# USB_ow.net
KiCad netlist of a schematic drawn in EAGLE
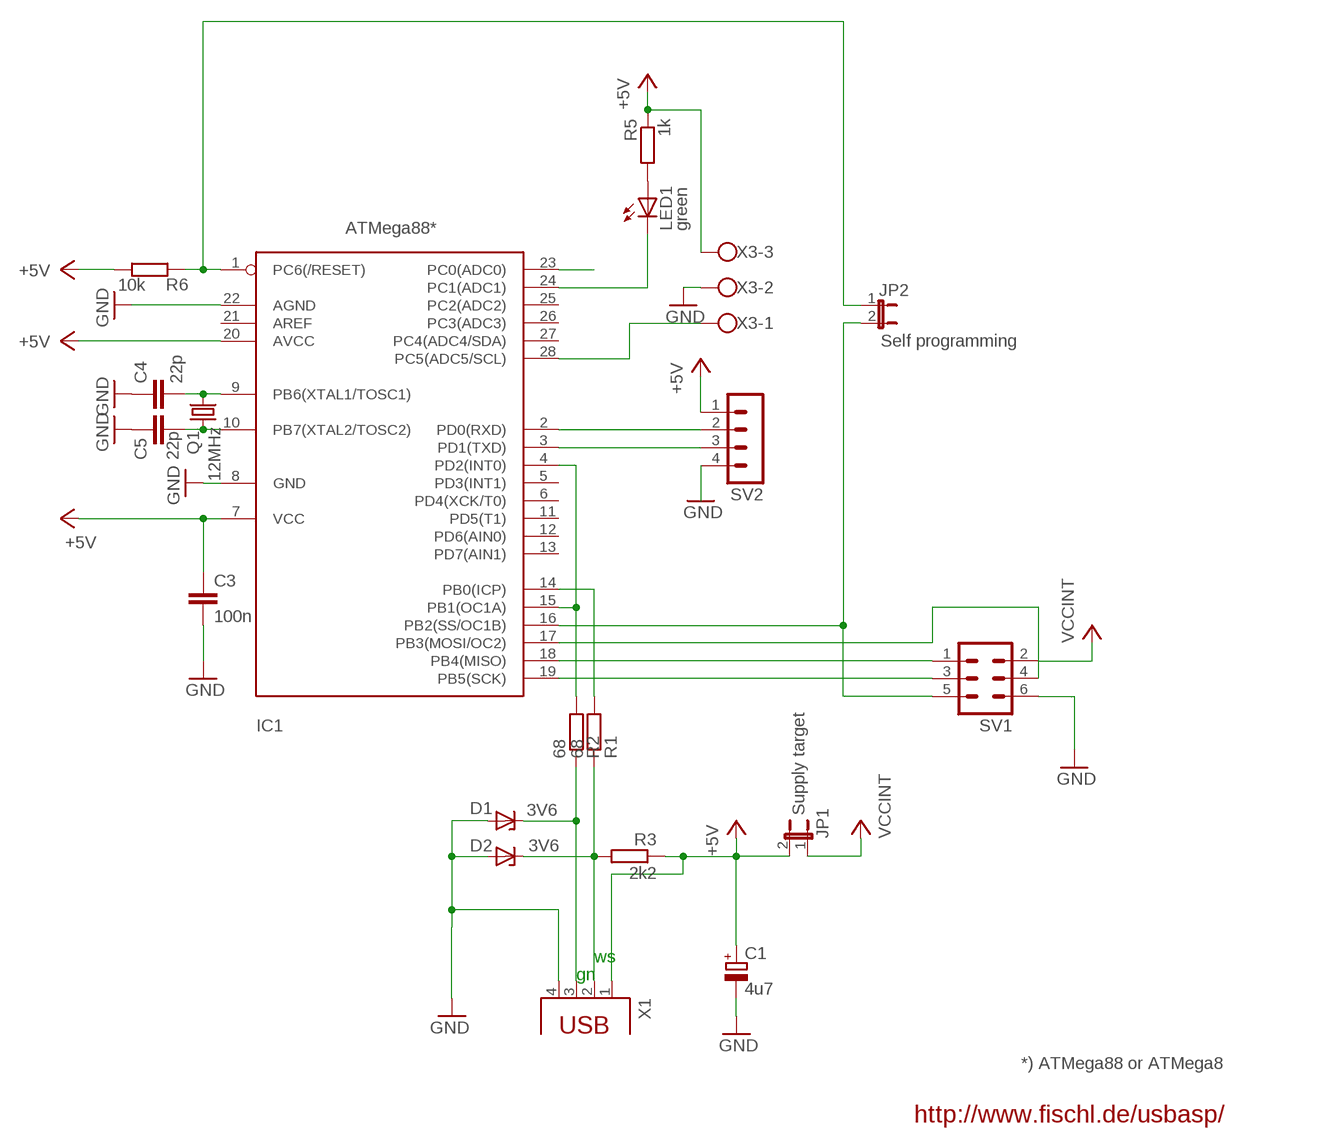
[diagram p0: schematic, sheet 1]

(export (version "E")
  (design (tool "Eeschema 10.0.6"))
  (components
    (comp (ref "C1")
      (value "4u7")
      (footprint "eagle-import:E2,5-5")
      (libsource (lib "eagle-import") (part "CPOL-EUE2.5-5"))
    )
    (comp (ref "C3")
      (value "100n")
      (footprint "eagle-import:C025-024X044")
      (libsource (lib "eagle-import") (part "C-EU025-024X044"))
    )
    (comp (ref "C4")
      (value "22p")
      (footprint "eagle-import:C025-024X044")
      (libsource (lib "eagle-import") (part "C-EU025-024X044"))
    )
    (comp (ref "C5")
      (value "22p")
      (footprint "eagle-import:C025-024X044")
      (libsource (lib "eagle-import") (part "C-EU025-024X044"))
    )
    (comp (ref "D1")
      (value "3V6")
      (footprint "eagle-import:DO34Z7")
      (libsource (lib "eagle-import") (part "ZENER-DIODEDO34-7"))
    )
    (comp (ref "D2")
      (value "3V6")
      (footprint "eagle-import:DO34Z7")
      (libsource (lib "eagle-import") (part "ZENER-DIODEDO34-7"))
    )
    (comp (ref "IC1")
      (value "ATMega88*")
      (footprint "eagle-import:DIL28-3")
      (libsource (lib "eagle-import") (part "MEGA8-P"))
    )
    (comp (ref "JP1")
      (value "Supply target")
      (footprint "eagle-import:JP1")
      (libsource (lib "eagle-import") (part "JP1E"))
    )
    (comp (ref "JP2")
      (value "Self programming")
      (footprint "eagle-import:JP1")
      (libsource (lib "eagle-import") (part "JP1E"))
    )
    (comp (ref "LED1")
      (value "green")
      (footprint "eagle-import:LED3MM")
      (libsource (lib "eagle-import") (part "LED3MM"))
    )
    (comp (ref "Q1")
      (value "12MHz")
      (footprint "eagle-import:HC49_S")
      (libsource (lib "eagle-import") (part "CRYTALHC49S"))
    )
    (comp (ref "R1")
      (value "68")
      (footprint "eagle-import:0207_10")
      (libsource (lib "eagle-import") (part "R-EU_0207/10"))
    )
    (comp (ref "R2")
      (value "68")
      (footprint "eagle-import:0207_10")
      (libsource (lib "eagle-import") (part "R-EU_0207/10"))
    )
    (comp (ref "R3")
      (value "2k2")
      (footprint "eagle-import:0207_10")
      (libsource (lib "eagle-import") (part "R-EU_0207/10"))
    )
    (comp (ref "R5")
      (value "1k")
      (footprint "eagle-import:0207_10")
      (libsource (lib "eagle-import") (part "R-EU_0207/10"))
    )
    (comp (ref "R6")
      (value "10k")
      (footprint "eagle-import:0207_10")
      (libsource (lib "eagle-import") (part "R-EU_0207/10"))
    )
    (comp (ref "SV1")
      (value "MA03-2")
      (footprint "eagle-import:MA03-2")
      (libsource (lib "eagle-import") (part "MA03-2"))
    )
    (comp (ref "SV2")
      (value "MA04-1")
      (footprint "eagle-import:MA04-1")
      (libsource (lib "eagle-import") (part "MA04-1"))
    )
    (comp (ref "X1")
      (value "PN61729")
      (footprint "eagle-import:PN61729")
      (libsource (lib "eagle-import") (part "PN61729"))
    )
    (comp (ref "X3")
      (value "W237-103")
      (footprint "eagle-import:W237-103")
      (fields (field (name "MPN") "237-103"))
      (libsource (lib "eagle-import") (part "W237-103"))
    )
  )
  (nets
    (net (code "1") (name "+5V") (class "Default")
      (node (ref "C1") (pin "+") (pinfunction "+_+") (pintype "passive"))
      (node (ref "C3") (pin "1") (pinfunction "1_1") (pintype "passive"))
      (node (ref "IC1") (pin "20") (pinfunction "AVCC_20") (pintype "bidirectional"))
      (node (ref "IC1") (pin "7") (pinfunction "VCC_7") (pintype "bidirectional"))
      (node (ref "JP1") (pin "2") (pinfunction "2_2") (pintype "passive"))
      (node (ref "R3") (pin "1") (pinfunction "1_1") (pintype "passive"))
      (node (ref "R5") (pin "1") (pinfunction "1_1") (pintype "passive"))
      (node (ref "R6") (pin "1") (pinfunction "1_1") (pintype "passive"))
      (node (ref "SV2") (pin "1") (pinfunction "1_1") (pintype "passive"))
      (node (ref "X1") (pin "1") (pinfunction "1_1") (pintype "bidirectional"))
      (node (ref "X3") (pin "3") (pinfunction "KL_3") (pintype "passive"))
    )
    (net (code "2") (name "GND") (class "Default")
      (node (ref "C1") (pin "-") (pinfunction "-_-") (pintype "passive"))
      (node (ref "C3") (pin "2") (pinfunction "2_2") (pintype "passive"))
      (node (ref "C4") (pin "1") (pinfunction "1_1") (pintype "passive"))
      (node (ref "C5") (pin "1") (pinfunction "1_1") (pintype "passive"))
      (node (ref "D1") (pin "A") (pinfunction "A_A") (pintype "passive"))
      (node (ref "D2") (pin "A") (pinfunction "A_A") (pintype "passive"))
      (node (ref "IC1") (pin "22") (pinfunction "AGND_22") (pintype "bidirectional"))
      (node (ref "IC1") (pin "8") (pinfunction "GND_8") (pintype "bidirectional"))
      (node (ref "SV1") (pin "6") (pinfunction "6_6") (pintype "passive"))
      (node (ref "SV2") (pin "4") (pinfunction "4_4") (pintype "passive"))
      (node (ref "X1") (pin "4") (pinfunction "4_4") (pintype "bidirectional"))
      (node (ref "X3") (pin "2") (pinfunction "KL_2") (pintype "passive"))
    )
    (net (code "3") (name "Net-(D1-PadC)") (class "Default")
      (node (ref "D1") (pin "C") (pinfunction "C_C") (pintype "passive"))
      (node (ref "R2") (pin "1") (pinfunction "1_1") (pintype "passive"))
      (node (ref "X1") (pin "3") (pinfunction "3_3") (pintype "bidirectional"))
    )
    (net (code "4") (name "Net-(D2-PadC)") (class "Default")
      (node (ref "D2") (pin "C") (pinfunction "C_C") (pintype "passive"))
      (node (ref "R1") (pin "1") (pinfunction "1_1") (pintype "passive"))
      (node (ref "R3") (pin "2") (pinfunction "2_2") (pintype "passive"))
      (node (ref "X1") (pin "2") (pinfunction "2_2") (pintype "bidirectional"))
    )
    (net (code "5") (name "Net-(IC1-PB0(ICP))") (class "Default")
      (node (ref "IC1") (pin "14") (pinfunction "PB0(ICP)_14") (pintype "bidirectional"))
      (node (ref "R1") (pin "2") (pinfunction "2_2") (pintype "passive"))
    )
    (net (code "6") (name "Net-(IC1-PB1(OC1A))") (class "Default")
      (node (ref "IC1") (pin "15") (pinfunction "PB1(OC1A)_15") (pintype "bidirectional"))
      (node (ref "IC1") (pin "4") (pinfunction "PD2(INT0)_4") (pintype "bidirectional"))
      (node (ref "R2") (pin "2") (pinfunction "2_2") (pintype "passive"))
    )
    (net (code "7") (name "Net-(IC1-PB2(SS{slash}OC1B))") (class "Default")
      (node (ref "IC1") (pin "16") (pinfunction "PB2(SS/OC1B)_16") (pintype "bidirectional"))
      (node (ref "JP2") (pin "2") (pinfunction "2_2") (pintype "passive"))
      (node (ref "SV1") (pin "5") (pinfunction "5_5") (pintype "passive"))
    )
    (net (code "8") (name "Net-(IC1-PB3(MOSI{slash}OC2))") (class "Default")
      (node (ref "IC1") (pin "17") (pinfunction "PB3(MOSI/OC2)_17") (pintype "bidirectional"))
      (node (ref "SV1") (pin "4") (pinfunction "4_4") (pintype "passive"))
    )
    (net (code "9") (name "Net-(IC1-PB4(MISO))") (class "Default")
      (node (ref "IC1") (pin "18") (pinfunction "PB4(MISO)_18") (pintype "bidirectional"))
      (node (ref "SV1") (pin "1") (pinfunction "1_1") (pintype "passive"))
    )
    (net (code "10") (name "Net-(IC1-PB5(SCK))") (class "Default")
      (node (ref "IC1") (pin "19") (pinfunction "PB5(SCK)_19") (pintype "bidirectional"))
      (node (ref "SV1") (pin "3") (pinfunction "3_3") (pintype "passive"))
    )
    (net (code "11") (name "Net-(IC1-PB6(XTAL1{slash}TOSC1))") (class "Default")
      (node (ref "C4") (pin "2") (pinfunction "2_2") (pintype "passive"))
      (node (ref "IC1") (pin "9") (pinfunction "PB6(XTAL1/TOSC1)_9") (pintype "bidirectional"))
      (node (ref "Q1") (pin "2") (pinfunction "2_2") (pintype "passive"))
    )
    (net (code "12") (name "Net-(IC1-PB7(XTAL2{slash}TOSC2))") (class "Default")
      (node (ref "C5") (pin "2") (pinfunction "2_2") (pintype "passive"))
      (node (ref "IC1") (pin "10") (pinfunction "PB7(XTAL2/TOSC2)_10") (pintype "bidirectional"))
      (node (ref "Q1") (pin "1") (pinfunction "1_1") (pintype "passive"))
    )
    (net (code "13") (name "Net-(IC1-PC1(ADC1))") (class "Default")
      (node (ref "IC1") (pin "24") (pinfunction "PC1(ADC1)_24") (pintype "bidirectional"))
      (node (ref "LED1") (pin "K") (pinfunction "C_K") (pintype "passive"))
    )
    (net (code "14") (name "Net-(IC1-PC5(ADC5{slash}SCL))") (class "Default")
      (node (ref "IC1") (pin "28") (pinfunction "PC5(ADC5/SCL)_28") (pintype "bidirectional"))
      (node (ref "X3") (pin "1") (pinfunction "KL_1") (pintype "passive"))
    )
    (net (code "15") (name "Net-(IC1-PC6({slash}RESET))") (class "Default")
      (node (ref "IC1") (pin "1") (pinfunction "PC6(/RESET)_1") (pintype "bidirectional"))
      (node (ref "JP2") (pin "1") (pinfunction "1_1") (pintype "passive"))
      (node (ref "R6") (pin "2") (pinfunction "2_2") (pintype "passive"))
    )
    (net (code "16") (name "Net-(IC1-PD0(RXD))") (class "Default")
      (node (ref "IC1") (pin "2") (pinfunction "PD0(RXD)_2") (pintype "bidirectional"))
      (node (ref "SV2") (pin "2") (pinfunction "2_2") (pintype "passive"))
    )
    (net (code "17") (name "Net-(IC1-PD1(TXD))") (class "Default")
      (node (ref "IC1") (pin "3") (pinfunction "PD1(TXD)_3") (pintype "bidirectional"))
      (node (ref "SV2") (pin "3") (pinfunction "3_3") (pintype "passive"))
    )
    (net (code "18") (name "Net-(LED1-PadA)") (class "Default")
      (node (ref "LED1") (pin "A") (pinfunction "A_A") (pintype "passive"))
      (node (ref "R5") (pin "2") (pinfunction "2_2") (pintype "passive"))
    )
    (net (code "19") (name "VCCINT") (class "Default")
      (node (ref "JP1") (pin "1") (pinfunction "1_1") (pintype "passive"))
      (node (ref "SV1") (pin "2") (pinfunction "2_2") (pintype "passive"))
    )
    (net (code "20") (name "unconnected-(IC1-AREF-Pad21)") (class "Default")
      (node (ref "IC1") (pin "21") (pinfunction "AREF_21") (pintype "bidirectional"))
    )
    (net (code "21") (name "unconnected-(IC1-PC0(ADC0)-Pad23)") (class "Default")
      (node (ref "IC1") (pin "23") (pinfunction "PC0(ADC0)_23") (pintype "bidirectional"))
    )
    (net (code "22") (name "unconnected-(IC1-PC2(ADC2)-Pad25)") (class "Default")
      (node (ref "IC1") (pin "25") (pinfunction "PC2(ADC2)_25") (pintype "bidirectional"))
    )
    (net (code "23") (name "unconnected-(IC1-PC3(ADC3)-Pad26)") (class "Default")
      (node (ref "IC1") (pin "26") (pinfunction "PC3(ADC3)_26") (pintype "bidirectional"))
    )
    (net (code "24") (name "unconnected-(IC1-PC4(ADC4{slash}SDA)-Pad27)") (class "Default")
      (node (ref "IC1") (pin "27") (pinfunction "PC4(ADC4/SDA)_27") (pintype "bidirectional"))
    )
    (net (code "25") (name "unconnected-(IC1-PD3(INT1)-Pad5)") (class "Default")
      (node (ref "IC1") (pin "5") (pinfunction "PD3(INT1)_5") (pintype "bidirectional"))
    )
    (net (code "26") (name "unconnected-(IC1-PD4(XCK{slash}T0)-Pad6)") (class "Default")
      (node (ref "IC1") (pin "6") (pinfunction "PD4(XCK/T0)_6") (pintype "bidirectional"))
    )
    (net (code "27") (name "unconnected-(IC1-PD5(T1)-Pad11)") (class "Default")
      (node (ref "IC1") (pin "11") (pinfunction "PD5(T1)_11") (pintype "bidirectional"))
    )
    (net (code "28") (name "unconnected-(IC1-PD6(AIN0)-Pad12)") (class "Default")
      (node (ref "IC1") (pin "12") (pinfunction "PD6(AIN0)_12") (pintype "bidirectional"))
    )
    (net (code "29") (name "unconnected-(IC1-PD7(AIN1)-Pad13)") (class "Default")
      (node (ref "IC1") (pin "13") (pinfunction "PD7(AIN1)_13") (pintype "bidirectional"))
    )
  )
)
